# comparator_module.net
KiCad netlist of a schematic drawn in EAGLE
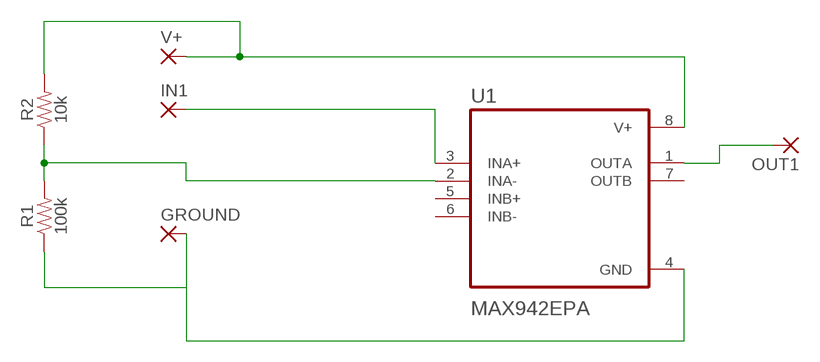
[diagram p0: schematic, sheet 1]

(export (version "E")
  (design (tool "Eeschema 10.0.6"))
  (components
    (comp (ref "GROUND")
      (value "3,81/1,4")
      (footprint "eagle-import:3,81_1,4")
      (libsource (lib "eagle-import") (part "3,81/1,4"))
    )
    (comp (ref "IN1")
      (value "3,81/1,4")
      (footprint "eagle-import:3,81_1,4")
      (libsource (lib "eagle-import") (part "3,81/1,4"))
    )
    (comp (ref "OUT1")
      (value "3,81/1,4")
      (footprint "eagle-import:3,81_1,4")
      (libsource (lib "eagle-import") (part "3,81/1,4"))
    )
    (comp (ref "R1")
      (value "100k")
      (footprint "eagle-import:AXIAL-0.3")
      (libsource (lib "eagle-import") (part "15KOHM-HORIZ-1/4W-5%"))
    )
    (comp (ref "R2")
      (value "10k")
      (footprint "eagle-import:AXIAL-0.3")
      (libsource (lib "eagle-import") (part "15KOHM-HORIZ-1/4W-5%"))
    )
    (comp (ref "U1")
      (value "MAX942EPA")
      (footprint "eagle-import:DIP794W47P254L991H457Q8")
      (fields
        (field (name "DIGI-KEY_PART_NUMBER") "MAX942EPA+-ND")
        (field (name "MF") "Maxim Integrated")
        (field (name "MP") "MAX942EPA+")
      )
      (libsource (lib "eagle-import") (part "MAX942EPA"))
    )
    (comp (ref "V+")
      (value "3,81/1,4")
      (footprint "eagle-import:3,81_1,4")
      (libsource (lib "eagle-import") (part "3,81/1,4"))
    )
  )
  (nets
    (net (code "1") (name "Net-(GROUND-P)") (class "Default")
      (node (ref "GROUND") (pin "1") (pinfunction "P_1") (pintype "passive"))
      (node (ref "R1") (pin "P$1") (pinfunction "1_P$1") (pintype "passive"))
      (node (ref "U1") (pin "4") (pinfunction "GND_4") (pintype "power_in"))
    )
    (net (code "2") (name "Net-(IN1-P)") (class "Default")
      (node (ref "IN1") (pin "1") (pinfunction "P_1") (pintype "passive"))
      (node (ref "U1") (pin "3") (pinfunction "INA+_3") (pintype "input"))
    )
    (net (code "3") (name "Net-(OUT1-P)") (class "Default")
      (node (ref "OUT1") (pin "1") (pinfunction "P_1") (pintype "passive"))
      (node (ref "U1") (pin "1") (pinfunction "OUTA_1") (pintype "output"))
    )
    (net (code "4") (name "Net-(R1-2)") (class "Default")
      (node (ref "R1") (pin "P$2") (pinfunction "2_P$2") (pintype "passive"))
      (node (ref "R2") (pin "P$1") (pinfunction "1_P$1") (pintype "passive"))
      (node (ref "U1") (pin "2") (pinfunction "INA-_2") (pintype "input"))
    )
    (net (code "5") (name "Net-(R2-2)") (class "Default")
      (node (ref "R2") (pin "P$2") (pinfunction "2_P$2") (pintype "passive"))
      (node (ref "U1") (pin "8") (pinfunction "V+_8") (pintype "power_in"))
      (node (ref "V+") (pin "1") (pinfunction "P_1") (pintype "passive"))
    )
    (net (code "6") (name "unconnected-(U1-INB+-Pad5)") (class "Default")
      (node (ref "U1") (pin "5") (pinfunction "INB+_5") (pintype "input"))
    )
    (net (code "7") (name "unconnected-(U1-INB--Pad6)") (class "Default")
      (node (ref "U1") (pin "6") (pinfunction "INB-_6") (pintype "input"))
    )
    (net (code "8") (name "unconnected-(U1-OUTB-Pad7)") (class "Default")
      (node (ref "U1") (pin "7") (pinfunction "OUTB_7") (pintype "output"))
    )
  )
)
